# Schema1.net
KiCad netlist of a schematic drawn in EAGLE
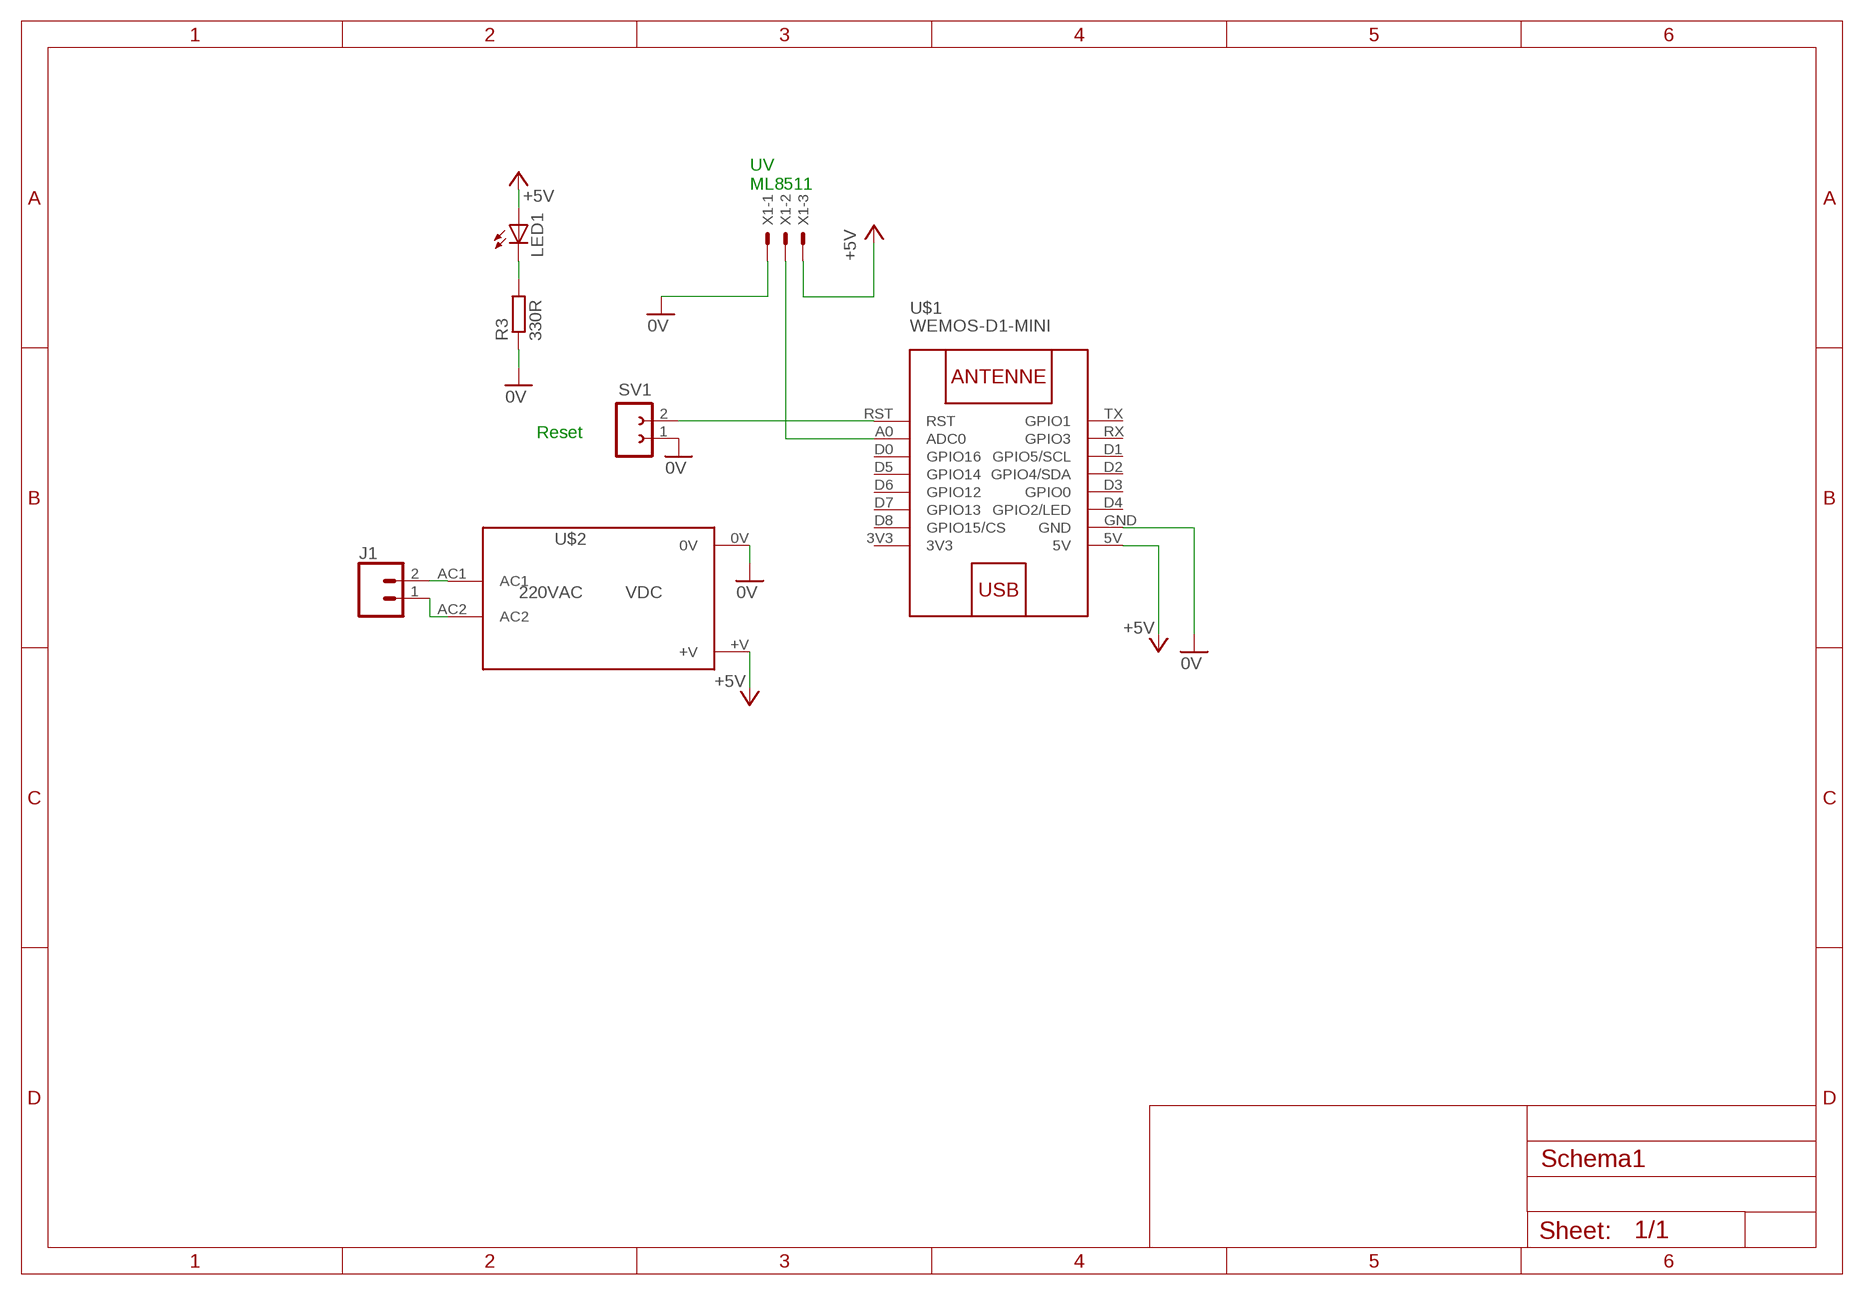
[diagram p0: schematic, sheet 1]

(export (version "E")
  (design (tool "Eeschema 10.0.6"))
  (components
    (comp (ref "J1")
      (value "CONN_025MM")
      (footprint "eagle-import:BORNIER_A_VIS_2_5.12MM")
      (libsource (lib "eagle-import") (part "CONN_025MM"))
    )
    (comp (ref "LED1")
      (value "LED5MM_F")
      (footprint "eagle-import:LED5MM")
      (libsource (lib "eagle-import") (part "LED5MM_F"))
    )
    (comp (ref "R3")
      (value "330R")
      (footprint "eagle-import:0207_10")
      (libsource (lib "eagle-import") (part "R-EU_0207/10"))
    )
    (comp (ref "SV1")
      (value "FE02-1")
      (footprint "eagle-import:FE02-1")
      (libsource (lib "eagle-import") (part "FE02-1"))
    )
    (comp (ref "U$1")
      (value "WEMOS-D1-MINI")
      (footprint "eagle-import:WEMOS-D1-MINI")
      (libsource (lib "eagle-import") (part "WEMOS-D1-MINI"))
    )
    (comp (ref "U$2")
      (value "TSP05-5V-3W")
      (footprint "eagle-import:TSP05-VDC-3W")
      (libsource (lib "eagle-import") (part "TSP05-5V-3W"))
    )
    (comp (ref "X1")
      (value "JST-XH-03-PIN-LONG-PAD")
      (footprint "eagle-import:JST-XH-03-PACKAGE-LONG-PAD")
      (libsource (lib "eagle-import") (part "JST-XH-03-PIN-LONG-PAD"))
    )
  )
  (nets
    (net (code "1") (name "+5V") (class "Default")
      (node (ref "LED1") (pin "A") (pinfunction "A_A") (pintype "passive"))
      (node (ref "U$1") (pin "5V") (pinfunction "5V_5V") (pintype "power_in"))
      (node (ref "U$2") (pin "+V") (pinfunction "+V_+V") (pintype "output"))
      (node (ref "X1") (pin "3") (pinfunction "S_3") (pintype "passive"))
    )
    (net (code "2") (name "/3V3") (class "Default")
      (node (ref "U$1") (pin "3V3") (pinfunction "3V3_3V3") (pintype "power_in"))
    )
    (net (code "3") (name "0V") (class "Default")
      (node (ref "R3") (pin "1") (pinfunction "1_1") (pintype "passive"))
      (node (ref "SV1") (pin "1") (pinfunction "1_1") (pintype "passive"))
      (node (ref "U$1") (pin "GND") (pinfunction "GND_GND") (pintype "power_in"))
      (node (ref "U$2") (pin "0V") (pinfunction "0V_0V") (pintype "output"))
      (node (ref "X1") (pin "1") (pinfunction "S_1") (pintype "passive"))
    )
    (net (code "4") (name "Net-(J1-Pad1)") (class "Default")
      (node (ref "J1") (pin "1") (pinfunction "1_1") (pintype "passive"))
      (node (ref "U$2") (pin "AC2") (pinfunction "AC2_AC2") (pintype "input"))
    )
    (net (code "5") (name "Net-(J1-Pad2)") (class "Default")
      (node (ref "J1") (pin "2") (pinfunction "2_2") (pintype "passive"))
      (node (ref "U$2") (pin "AC1") (pinfunction "AC1_AC1") (pintype "bidirectional"))
    )
    (net (code "6") (name "Net-(LED1-C)") (class "Default")
      (node (ref "LED1") (pin "K") (pinfunction "C_K") (pintype "passive"))
      (node (ref "R3") (pin "2") (pinfunction "2_2") (pintype "passive"))
    )
    (net (code "7") (name "Net-(SV1-Pad2)") (class "Default")
      (node (ref "SV1") (pin "2") (pinfunction "2_2") (pintype "passive"))
      (node (ref "U$1") (pin "RST") (pinfunction "RST_RST") (pintype "bidirectional"))
    )
    (net (code "8") (name "Net-(U$1-ADC0)") (class "Default")
      (node (ref "U$1") (pin "A0") (pinfunction "ADC0_A0") (pintype "bidirectional"))
      (node (ref "X1") (pin "2") (pinfunction "S_2") (pintype "passive"))
    )
    (net (code "9") (name "unconnected-(U$1-GPIO0-PadD3)") (class "Default")
      (node (ref "U$1") (pin "D3") (pinfunction "GPIO0_D3") (pintype "bidirectional"))
    )
    (net (code "10") (name "unconnected-(U$1-GPIO1-PadTX)") (class "Default")
      (node (ref "U$1") (pin "TX") (pinfunction "GPIO1_TX") (pintype "bidirectional"))
    )
    (net (code "11") (name "unconnected-(U$1-GPIO2{slash}LED-PadD4)") (class "Default")
      (node (ref "U$1") (pin "D4") (pinfunction "GPIO2/LED_D4") (pintype "bidirectional"))
    )
    (net (code "12") (name "unconnected-(U$1-GPIO3-PadRX)") (class "Default")
      (node (ref "U$1") (pin "RX") (pinfunction "GPIO3_RX") (pintype "bidirectional"))
    )
    (net (code "13") (name "unconnected-(U$1-GPIO4{slash}SDA-PadD2)") (class "Default")
      (node (ref "U$1") (pin "D2") (pinfunction "GPIO4/SDA_D2") (pintype "bidirectional"))
    )
    (net (code "14") (name "unconnected-(U$1-GPIO5{slash}SCL-PadD1)") (class "Default")
      (node (ref "U$1") (pin "D1") (pinfunction "GPIO5/SCL_D1") (pintype "bidirectional"))
    )
    (net (code "15") (name "unconnected-(U$1-GPIO12-PadD6)") (class "Default")
      (node (ref "U$1") (pin "D6") (pinfunction "GPIO12_D6") (pintype "bidirectional"))
    )
    (net (code "16") (name "unconnected-(U$1-GPIO13-PadD7)") (class "Default")
      (node (ref "U$1") (pin "D7") (pinfunction "GPIO13_D7") (pintype "bidirectional"))
    )
    (net (code "17") (name "unconnected-(U$1-GPIO14-PadD5)") (class "Default")
      (node (ref "U$1") (pin "D5") (pinfunction "GPIO14_D5") (pintype "bidirectional"))
    )
    (net (code "18") (name "unconnected-(U$1-GPIO15{slash}CS-PadD8)") (class "Default")
      (node (ref "U$1") (pin "D8") (pinfunction "GPIO15/CS_D8") (pintype "bidirectional"))
    )
    (net (code "19") (name "unconnected-(U$1-GPIO16-PadD0)") (class "Default")
      (node (ref "U$1") (pin "D0") (pinfunction "GPIO16_D0") (pintype "bidirectional"))
    )
  )
)
